# hbridge-motherboard.net
KiCad netlist of a schematic drawn in EAGLE
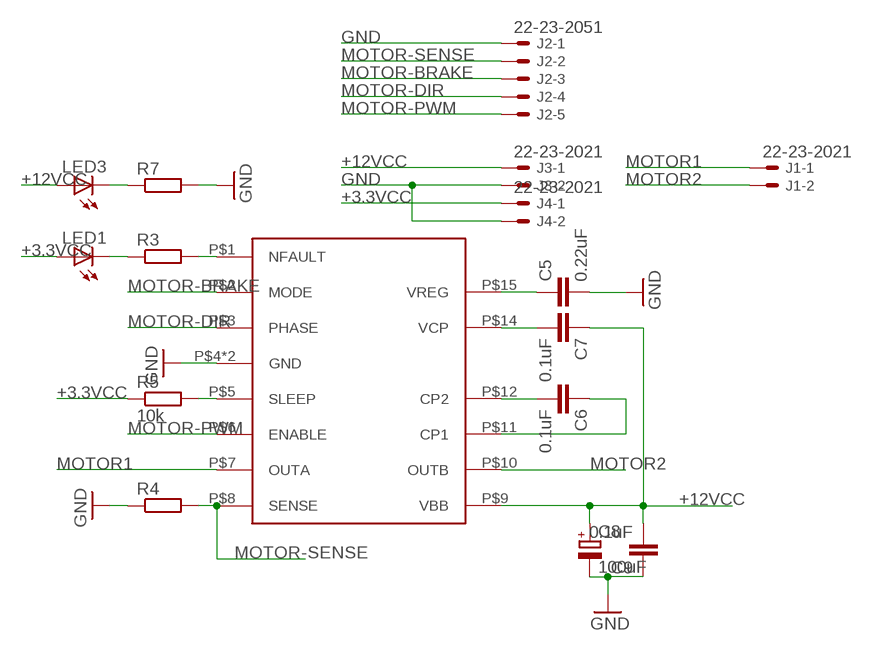
[diagram p0: schematic, sheet 1]

(export (version "E")
  (design (tool "Eeschema 10.0.6"))
  (components
    (comp (ref "C5")
      (value "0.22uF")
      (footprint "eagle-import:C050-024X044")
      (libsource (lib "eagle-import") (part "C-EU050-024X044"))
    )
    (comp (ref "C6")
      (value "0.1uF")
      (footprint "eagle-import:C050-024X044")
      (libsource (lib "eagle-import") (part "C-EU050-024X044"))
    )
    (comp (ref "C7")
      (value "0.1uF")
      (footprint "eagle-import:C050-024X044")
      (libsource (lib "eagle-import") (part "C-EU050-024X044"))
    )
    (comp (ref "C8")
      (value "100uF")
      (footprint "eagle-import:E3,5-8")
      (libsource (lib "eagle-import") (part "CPOL-EUE3.5-8"))
    )
    (comp (ref "C9")
      (value "0.1uF")
      (footprint "eagle-import:C050-024X044")
      (libsource (lib "eagle-import") (part "C-EU050-024X044"))
    )
    (comp (ref "J1")
      (value "22-23-2021")
      (footprint "eagle-import:22-23-2021")
      (fields (field (name "MF") "MOLEX"))
      (libsource (lib "eagle-import") (part "22-23-2021"))
    )
    (comp (ref "J2")
      (value "22-23-2051")
      (footprint "eagle-import:22-23-2051")
      (fields (field (name "MF") "MOLEX"))
      (libsource (lib "eagle-import") (part "22-23-2051"))
    )
    (comp (ref "J3")
      (value "22-23-2021")
      (footprint "eagle-import:22-23-2021")
      (fields (field (name "MF") "MOLEX"))
      (libsource (lib "eagle-import") (part "22-23-2021"))
    )
    (comp (ref "J4")
      (value "22-23-2021")
      (footprint "eagle-import:22-23-2021")
      (fields (field (name "MF") "MOLEX"))
      (libsource (lib "eagle-import") (part "22-23-2021"))
    )
    (comp (ref "LED1")
      (value "LED3MM")
      (footprint "eagle-import:LED3MM")
      (libsource (lib "eagle-import") (part "LED3MM"))
    )
    (comp (ref "LED3")
      (value "LED3MM")
      (footprint "eagle-import:LED3MM")
      (libsource (lib "eagle-import") (part "LED3MM"))
    )
    (comp (ref "R3")
      (value "R-EU_0207/7")
      (footprint "eagle-import:0207_7")
      (libsource (lib "eagle-import") (part "R-EU_0207/7"))
    )
    (comp (ref "R4")
      (value "R-EU_0207/7")
      (footprint "eagle-import:0207_7")
      (libsource (lib "eagle-import") (part "R-EU_0207/7"))
    )
    (comp (ref "R5")
      (value "10k")
      (footprint "eagle-import:0207_7")
      (libsource (lib "eagle-import") (part "R-EU_0207/7"))
    )
    (comp (ref "R7")
      (value "R-EU_0207/7")
      (footprint "eagle-import:0207_7")
      (libsource (lib "eagle-import") (part "R-EU_0207/7"))
    )
    (comp (ref "U$1")
      (value "A3950-DIL")
      (footprint "eagle-import:DIL16")
      (libsource (lib "eagle-import") (part "A3950-DIL"))
    )
  )
  (nets
    (net (code "1") (name "/+3.3VCC") (class "Default")
      (node (ref "J4") (pin "1") (pinfunction "S_1") (pintype "passive"))
      (node (ref "LED1") (pin "A") (pinfunction "A_A") (pintype "passive"))
      (node (ref "R5") (pin "1") (pinfunction "1_1") (pintype "passive"))
    )
    (net (code "2") (name "/+12VCC") (class "Default")
      (node (ref "C7") (pin "1") (pinfunction "1_1") (pintype "passive"))
      (node (ref "C8") (pin "+") (pinfunction "+_+") (pintype "passive"))
      (node (ref "C9") (pin "2") (pinfunction "2_2") (pintype "passive"))
      (node (ref "J3") (pin "1") (pinfunction "S_1") (pintype "passive"))
      (node (ref "LED3") (pin "A") (pinfunction "A_A") (pintype "passive"))
      (node (ref "U$1") (pin "P$9") (pinfunction "VBB_P$9") (pintype "bidirectional"))
    )
    (net (code "3") (name "/MOTOR-BRAKE") (class "Default")
      (node (ref "J2") (pin "3") (pinfunction "S_3") (pintype "passive"))
      (node (ref "U$1") (pin "P$2") (pinfunction "MODE_P$2") (pintype "bidirectional"))
    )
    (net (code "4") (name "/MOTOR-DIR") (class "Default")
      (node (ref "J2") (pin "4") (pinfunction "S_4") (pintype "passive"))
      (node (ref "U$1") (pin "P$3") (pinfunction "PHASE_P$3") (pintype "bidirectional"))
    )
    (net (code "5") (name "/MOTOR-PWM") (class "Default")
      (node (ref "J2") (pin "5") (pinfunction "S_5") (pintype "passive"))
      (node (ref "U$1") (pin "P$6") (pinfunction "ENABLE_P$6") (pintype "bidirectional"))
    )
    (net (code "6") (name "/MOTOR-SENSE") (class "Default")
      (node (ref "J2") (pin "2") (pinfunction "S_2") (pintype "passive"))
      (node (ref "R4") (pin "2") (pinfunction "2_2") (pintype "passive"))
      (node (ref "U$1") (pin "P$8") (pinfunction "SENSE_P$8") (pintype "bidirectional"))
    )
    (net (code "7") (name "/MOTOR1") (class "Default")
      (node (ref "J1") (pin "1") (pinfunction "S_1") (pintype "passive"))
      (node (ref "U$1") (pin "P$7") (pinfunction "OUTA_P$7") (pintype "bidirectional"))
    )
    (net (code "8") (name "/MOTOR2") (class "Default")
      (node (ref "J1") (pin "2") (pinfunction "S_2") (pintype "passive"))
      (node (ref "U$1") (pin "P$10") (pinfunction "OUTB_P$10") (pintype "bidirectional"))
    )
    (net (code "9") (name "GND") (class "Default")
      (node (ref "C5") (pin "2") (pinfunction "2_2") (pintype "passive"))
      (node (ref "C8") (pin "-") (pinfunction "-_-") (pintype "passive"))
      (node (ref "C9") (pin "1") (pinfunction "1_1") (pintype "passive"))
      (node (ref "J2") (pin "1") (pinfunction "S_1") (pintype "passive"))
      (node (ref "J3") (pin "2") (pinfunction "S_2") (pintype "passive"))
      (node (ref "J4") (pin "2") (pinfunction "S_2") (pintype "passive"))
      (node (ref "R4") (pin "1") (pinfunction "1_1") (pintype "passive"))
      (node (ref "R7") (pin "2") (pinfunction "2_2") (pintype "passive"))
      (node (ref "U$1") (pin "P$13") (pinfunction "GND_P$13") (pintype "bidirectional"))
      (node (ref "U$1") (pin "P$4") (pinfunction "GND_P$4") (pintype "bidirectional"))
    )
    (net (code "10") (name "Net-(LED1-C)") (class "Default")
      (node (ref "LED1") (pin "K") (pinfunction "C_K") (pintype "passive"))
      (node (ref "R3") (pin "1") (pinfunction "1_1") (pintype "passive"))
    )
    (net (code "11") (name "Net-(LED3-C)") (class "Default")
      (node (ref "LED3") (pin "K") (pinfunction "C_K") (pintype "passive"))
      (node (ref "R7") (pin "1") (pinfunction "1_1") (pintype "passive"))
    )
    (net (code "12") (name "Net-(U$1-CP1)") (class "Default")
      (node (ref "C6") (pin "1") (pinfunction "1_1") (pintype "passive"))
      (node (ref "U$1") (pin "P$11") (pinfunction "CP1_P$11") (pintype "bidirectional"))
    )
    (net (code "13") (name "Net-(U$1-CP2)") (class "Default")
      (node (ref "C6") (pin "2") (pinfunction "2_2") (pintype "passive"))
      (node (ref "U$1") (pin "P$12") (pinfunction "CP2_P$12") (pintype "bidirectional"))
    )
    (net (code "14") (name "Net-(U$1-NFAULT)") (class "Default")
      (node (ref "R3") (pin "2") (pinfunction "2_2") (pintype "passive"))
      (node (ref "U$1") (pin "P$1") (pinfunction "NFAULT_P$1") (pintype "bidirectional"))
    )
    (net (code "15") (name "Net-(U$1-SLEEP)") (class "Default")
      (node (ref "R5") (pin "2") (pinfunction "2_2") (pintype "passive"))
      (node (ref "U$1") (pin "P$5") (pinfunction "SLEEP_P$5") (pintype "bidirectional"))
    )
    (net (code "16") (name "Net-(U$1-VCP)") (class "Default")
      (node (ref "C7") (pin "2") (pinfunction "2_2") (pintype "passive"))
      (node (ref "U$1") (pin "P$14") (pinfunction "VCP_P$14") (pintype "bidirectional"))
    )
    (net (code "17") (name "Net-(U$1-VREG)") (class "Default")
      (node (ref "C5") (pin "1") (pinfunction "1_1") (pintype "passive"))
      (node (ref "U$1") (pin "P$15") (pinfunction "VREG_P$15") (pintype "bidirectional"))
    )
  )
)
